# 60.net
KiCad netlist of a schematic drawn in EasyEDA Pro
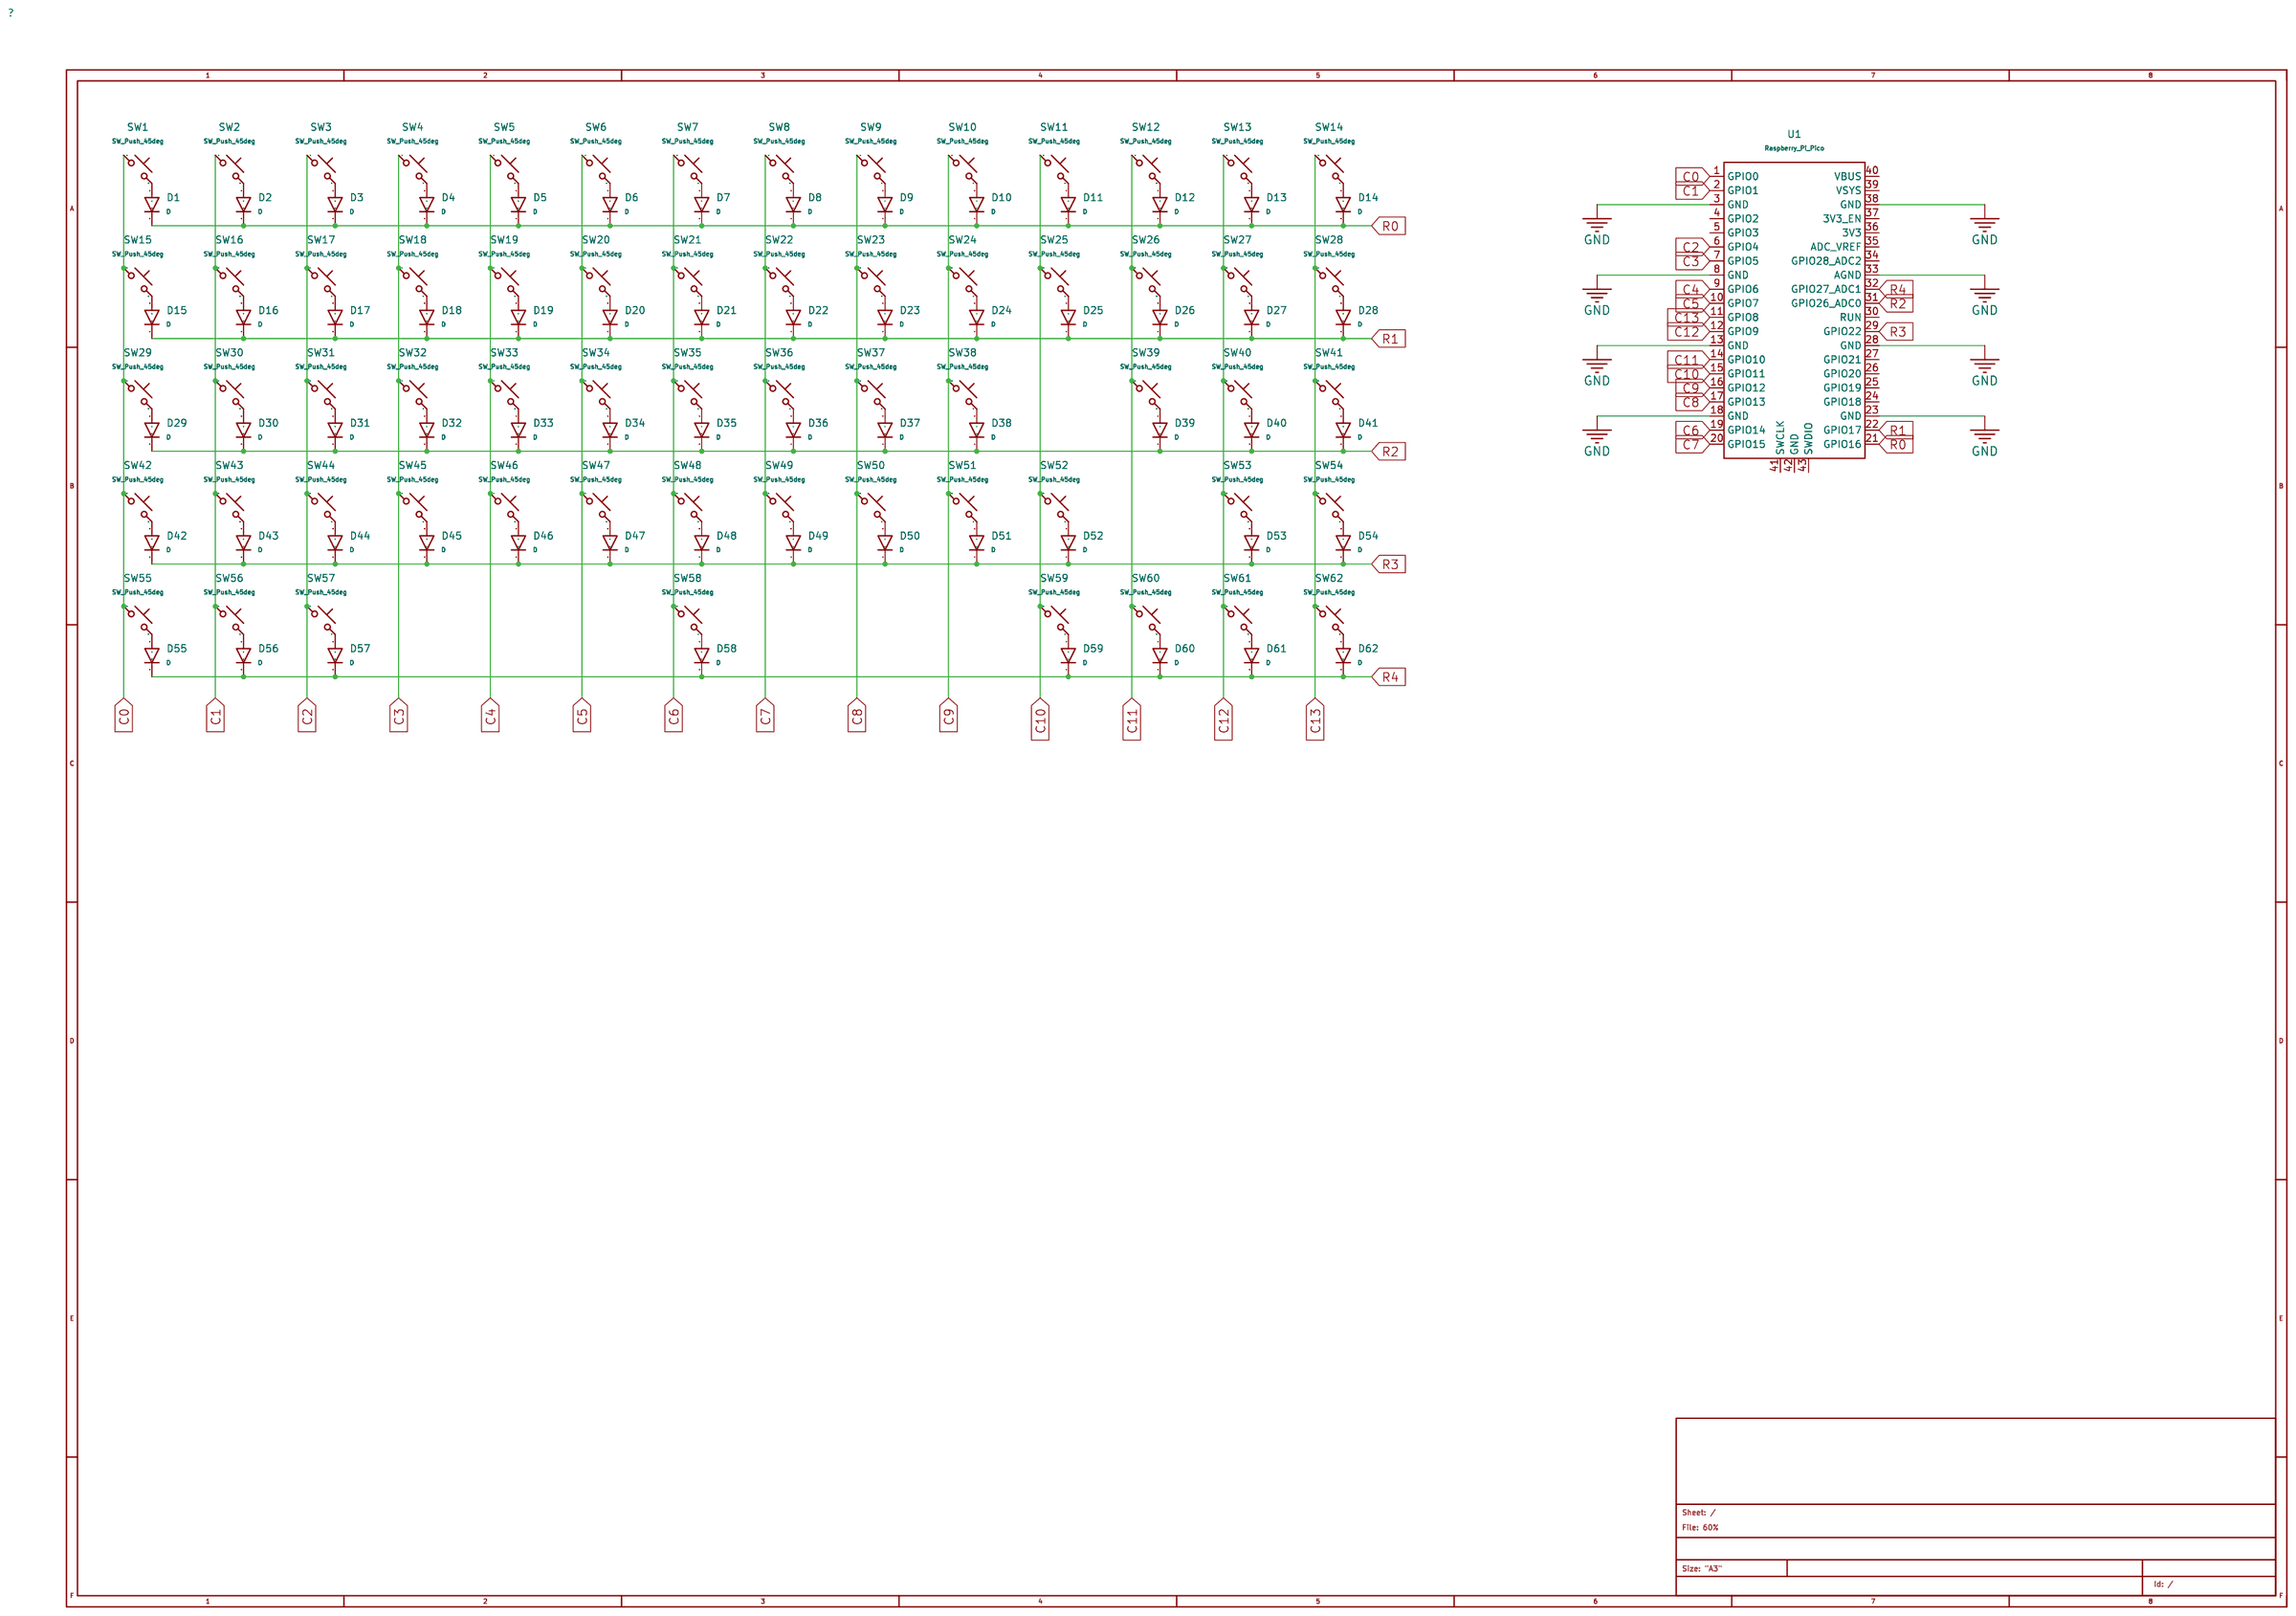
[diagram p0: schematic sheet]

(export (version "E")
  (design (tool "Eeschema 10.0.6"))
  (components
    (comp (ref "D1")
      (value "D")
      (footprint "easyedapro:Diode_DO-35")
      (description "Diode")
      (libsource (lib "easyedapro") (part "Device_D"))
    )
    (comp (ref "D2")
      (value "D")
      (footprint "easyedapro:Diode_DO-35")
      (description "Diode")
      (libsource (lib "easyedapro") (part "Device_D"))
    )
    (comp (ref "D3")
      (value "D")
      (footprint "easyedapro:Diode_DO-35")
      (description "Diode")
      (libsource (lib "easyedapro") (part "Device_D"))
    )
    (comp (ref "D4")
      (value "D")
      (footprint "easyedapro:Diode_DO-35")
      (description "Diode")
      (libsource (lib "easyedapro") (part "Device_D"))
    )
    (comp (ref "D5")
      (value "D")
      (footprint "easyedapro:Diode_DO-35")
      (description "Diode")
      (libsource (lib "easyedapro") (part "Device_D"))
    )
    (comp (ref "D6")
      (value "D")
      (footprint "easyedapro:Diode_DO-35")
      (description "Diode")
      (libsource (lib "easyedapro") (part "Device_D"))
    )
    (comp (ref "D7")
      (value "D")
      (footprint "easyedapro:Diode_DO-35")
      (description "Diode")
      (libsource (lib "easyedapro") (part "Device_D"))
    )
    (comp (ref "D8")
      (value "D")
      (footprint "easyedapro:Diode_DO-35")
      (description "Diode")
      (libsource (lib "easyedapro") (part "Device_D"))
    )
    (comp (ref "D9")
      (value "D")
      (footprint "easyedapro:Diode_DO-35")
      (description "Diode")
      (libsource (lib "easyedapro") (part "Device_D"))
    )
    (comp (ref "D10")
      (value "D")
      (footprint "easyedapro:Diode_DO-35")
      (description "Diode")
      (libsource (lib "easyedapro") (part "Device_D"))
    )
    (comp (ref "D11")
      (value "D")
      (footprint "easyedapro:Diode_DO-35")
      (description "Diode")
      (libsource (lib "easyedapro") (part "Device_D"))
    )
    (comp (ref "D12")
      (value "D")
      (footprint "easyedapro:Diode_DO-35")
      (description "Diode")
      (libsource (lib "easyedapro") (part "Device_D"))
    )
    (comp (ref "D13")
      (value "D")
      (footprint "easyedapro:Diode_DO-35")
      (description "Diode")
      (libsource (lib "easyedapro") (part "Device_D"))
    )
    (comp (ref "D14")
      (value "D")
      (footprint "easyedapro:Diode_DO-35")
      (description "Diode")
      (libsource (lib "easyedapro") (part "Device_D"))
    )
    (comp (ref "D15")
      (value "D")
      (footprint "easyedapro:Diode_DO-35")
      (description "Diode")
      (libsource (lib "easyedapro") (part "Device_D"))
    )
    (comp (ref "D16")
      (value "D")
      (footprint "easyedapro:Diode_DO-35")
      (description "Diode")
      (libsource (lib "easyedapro") (part "Device_D"))
    )
    (comp (ref "D17")
      (value "D")
      (footprint "easyedapro:Diode_DO-35")
      (description "Diode")
      (libsource (lib "easyedapro") (part "Device_D"))
    )
    (comp (ref "D18")
      (value "D")
      (footprint "easyedapro:Diode_DO-35")
      (description "Diode")
      (libsource (lib "easyedapro") (part "Device_D"))
    )
    (comp (ref "D19")
      (value "D")
      (footprint "easyedapro:Diode_DO-35")
      (description "Diode")
      (libsource (lib "easyedapro") (part "Device_D"))
    )
    (comp (ref "D20")
      (value "D")
      (footprint "easyedapro:Diode_DO-35")
      (description "Diode")
      (libsource (lib "easyedapro") (part "Device_D"))
    )
    (comp (ref "D21")
      (value "D")
      (footprint "easyedapro:Diode_DO-35")
      (description "Diode")
      (libsource (lib "easyedapro") (part "Device_D"))
    )
    (comp (ref "D22")
      (value "D")
      (footprint "easyedapro:Diode_DO-35")
      (description "Diode")
      (libsource (lib "easyedapro") (part "Device_D"))
    )
    (comp (ref "D23")
      (value "D")
      (footprint "easyedapro:Diode_DO-35")
      (description "Diode")
      (libsource (lib "easyedapro") (part "Device_D"))
    )
    (comp (ref "D24")
      (value "D")
      (footprint "easyedapro:Diode_DO-35")
      (description "Diode")
      (libsource (lib "easyedapro") (part "Device_D"))
    )
    (comp (ref "D25")
      (value "D")
      (footprint "easyedapro:Diode_DO-35")
      (description "Diode")
      (libsource (lib "easyedapro") (part "Device_D"))
    )
    (comp (ref "D26")
      (value "D")
      (footprint "easyedapro:Diode_DO-35")
      (description "Diode")
      (libsource (lib "easyedapro") (part "Device_D"))
    )
    (comp (ref "D27")
      (value "D")
      (footprint "easyedapro:Diode_DO-35")
      (description "Diode")
      (libsource (lib "easyedapro") (part "Device_D"))
    )
    (comp (ref "D28")
      (value "D")
      (footprint "easyedapro:Diode_DO-35")
      (description "Diode")
      (libsource (lib "easyedapro") (part "Device_D"))
    )
    (comp (ref "D29")
      (value "D")
      (footprint "easyedapro:Diode_DO-35")
      (description "Diode")
      (libsource (lib "easyedapro") (part "Device_D"))
    )
    (comp (ref "D30")
      (value "D")
      (footprint "easyedapro:Diode_DO-35")
      (description "Diode")
      (libsource (lib "easyedapro") (part "Device_D"))
    )
    (comp (ref "D31")
      (value "D")
      (footprint "easyedapro:Diode_DO-35")
      (description "Diode")
      (libsource (lib "easyedapro") (part "Device_D"))
    )
    (comp (ref "D32")
      (value "D")
      (footprint "easyedapro:Diode_DO-35")
      (description "Diode")
      (libsource (lib "easyedapro") (part "Device_D"))
    )
    (comp (ref "D33")
      (value "D")
      (footprint "easyedapro:Diode_DO-35")
      (description "Diode")
      (libsource (lib "easyedapro") (part "Device_D"))
    )
    (comp (ref "D34")
      (value "D")
      (footprint "easyedapro:Diode_DO-35")
      (description "Diode")
      (libsource (lib "easyedapro") (part "Device_D"))
    )
    (comp (ref "D35")
      (value "D")
      (footprint "easyedapro:Diode_DO-35")
      (description "Diode")
      (libsource (lib "easyedapro") (part "Device_D"))
    )
    (comp (ref "D36")
      (value "D")
      (footprint "easyedapro:Diode_DO-35")
      (description "Diode")
      (libsource (lib "easyedapro") (part "Device_D"))
    )
    (comp (ref "D37")
      (value "D")
      (footprint "easyedapro:Diode_DO-35")
      (description "Diode")
      (libsource (lib "easyedapro") (part "Device_D"))
    )
    (comp (ref "D38")
      (value "D")
      (footprint "easyedapro:Diode_DO-35")
      (description "Diode")
      (libsource (lib "easyedapro") (part "Device_D"))
    )
    (comp (ref "D39")
      (value "D")
      (footprint "easyedapro:Diode_DO-35")
      (description "Diode")
      (libsource (lib "easyedapro") (part "Device_D"))
    )
    (comp (ref "D40")
      (value "D")
      (footprint "easyedapro:Diode_DO-35")
      (description "Diode")
      (libsource (lib "easyedapro") (part "Device_D"))
    )
    (comp (ref "D41")
      (value "D")
      (footprint "easyedapro:Diode_DO-35")
      (description "Diode")
      (libsource (lib "easyedapro") (part "Device_D"))
    )
    (comp (ref "D42")
      (value "D")
      (footprint "easyedapro:Diode_DO-35")
      (description "Diode")
      (libsource (lib "easyedapro") (part "Device_D"))
    )
    (comp (ref "D43")
      (value "D")
      (footprint "easyedapro:Diode_DO-35")
      (description "Diode")
      (libsource (lib "easyedapro") (part "Device_D"))
    )
    (comp (ref "D44")
      (value "D")
      (footprint "easyedapro:Diode_DO-35")
      (description "Diode")
      (libsource (lib "easyedapro") (part "Device_D"))
    )
    (comp (ref "D45")
      (value "D")
      (footprint "easyedapro:Diode_DO-35")
      (description "Diode")
      (libsource (lib "easyedapro") (part "Device_D"))
    )
    (comp (ref "D46")
      (value "D")
      (footprint "easyedapro:Diode_DO-35")
      (description "Diode")
      (libsource (lib "easyedapro") (part "Device_D"))
    )
    (comp (ref "D47")
      (value "D")
      (footprint "easyedapro:Diode_DO-35")
      (description "Diode")
      (libsource (lib "easyedapro") (part "Device_D"))
    )
    (comp (ref "D48")
      (value "D")
      (footprint "easyedapro:Diode_DO-35")
      (description "Diode")
      (libsource (lib "easyedapro") (part "Device_D"))
    )
    (comp (ref "D49")
      (value "D")
      (footprint "easyedapro:Diode_DO-35")
      (description "Diode")
      (libsource (lib "easyedapro") (part "Device_D"))
    )
    (comp (ref "D50")
      (value "D")
      (footprint "easyedapro:Diode_DO-35")
      (description "Diode")
      (libsource (lib "easyedapro") (part "Device_D"))
    )
    (comp (ref "D51")
      (value "D")
      (footprint "easyedapro:Diode_DO-35")
      (description "Diode")
      (libsource (lib "easyedapro") (part "Device_D"))
    )
    (comp (ref "D52")
      (value "D")
      (footprint "easyedapro:Diode_DO-35")
      (description "Diode")
      (libsource (lib "easyedapro") (part "Device_D"))
    )
    (comp (ref "D53")
      (value "D")
      (footprint "easyedapro:Diode_DO-35")
      (description "Diode")
      (libsource (lib "easyedapro") (part "Device_D"))
    )
    (comp (ref "D54")
      (value "D")
      (footprint "easyedapro:Diode_DO-35")
      (description "Diode")
      (libsource (lib "easyedapro") (part "Device_D"))
    )
    (comp (ref "D55")
      (value "D")
      (footprint "easyedapro:Diode_DO-35")
      (description "Diode")
      (libsource (lib "easyedapro") (part "Device_D"))
    )
    (comp (ref "D56")
      (value "D")
      (footprint "easyedapro:Diode_DO-35")
      (description "Diode")
      (libsource (lib "easyedapro") (part "Device_D"))
    )
    (comp (ref "D57")
      (value "D")
      (footprint "easyedapro:Diode_DO-35")
      (description "Diode")
      (libsource (lib "easyedapro") (part "Device_D"))
    )
    (comp (ref "D58")
      (value "D")
      (footprint "easyedapro:Diode_DO-35")
      (description "Diode")
      (libsource (lib "easyedapro") (part "Device_D"))
    )
    (comp (ref "D59")
      (value "D")
      (footprint "easyedapro:Diode_DO-35")
      (description "Diode")
      (libsource (lib "easyedapro") (part "Device_D"))
    )
    (comp (ref "D60")
      (value "D")
      (footprint "easyedapro:Diode_DO-35")
      (description "Diode")
      (libsource (lib "easyedapro") (part "Device_D"))
    )
    (comp (ref "D61")
      (value "D")
      (footprint "easyedapro:Diode_DO-35")
      (description "Diode")
      (libsource (lib "easyedapro") (part "Device_D"))
    )
    (comp (ref "D62")
      (value "D")
      (footprint "easyedapro:Diode_DO-35")
      (description "Diode")
      (libsource (lib "easyedapro") (part "Device_D"))
    )
    (comp (ref "SW1")
      (value "SW_Push_45deg")
      (footprint "easyedapro:MX_PCB_1.00u")
      (description "Push button switch, normally open, two pins, 45° tilted")
      (libsource (lib "easyedapro") (part "Switch_SW_Push_45deg"))
    )
    (comp (ref "SW2")
      (value "SW_Push_45deg")
      (footprint "easyedapro:MX_PCB_1.00u")
      (description "Push button switch, normally open, two pins, 45° tilted")
      (libsource (lib "easyedapro") (part "Switch_SW_Push_45deg"))
    )
    (comp (ref "SW3")
      (value "SW_Push_45deg")
      (footprint "easyedapro:MX_PCB_1.00u")
      (description "Push button switch, normally open, two pins, 45° tilted")
      (libsource (lib "easyedapro") (part "Switch_SW_Push_45deg"))
    )
    (comp (ref "SW4")
      (value "SW_Push_45deg")
      (footprint "easyedapro:MX_PCB_1.00u")
      (description "Push button switch, normally open, two pins, 45° tilted")
      (libsource (lib "easyedapro") (part "Switch_SW_Push_45deg"))
    )
    (comp (ref "SW5")
      (value "SW_Push_45deg")
      (footprint "easyedapro:MX_PCB_1.00u")
      (description "Push button switch, normally open, two pins, 45° tilted")
      (libsource (lib "easyedapro") (part "Switch_SW_Push_45deg"))
    )
    (comp (ref "SW6")
      (value "SW_Push_45deg")
      (footprint "easyedapro:MX_PCB_1.00u")
      (description "Push button switch, normally open, two pins, 45° tilted")
      (libsource (lib "easyedapro") (part "Switch_SW_Push_45deg"))
    )
    (comp (ref "SW7")
      (value "SW_Push_45deg")
      (footprint "easyedapro:MX_PCB_1.00u")
      (description "Push button switch, normally open, two pins, 45° tilted")
      (libsource (lib "easyedapro") (part "Switch_SW_Push_45deg"))
    )
    (comp (ref "SW8")
      (value "SW_Push_45deg")
      (footprint "easyedapro:MX_PCB_1.00u")
      (description "Push button switch, normally open, two pins, 45° tilted")
      (libsource (lib "easyedapro") (part "Switch_SW_Push_45deg"))
    )
    (comp (ref "SW9")
      (value "SW_Push_45deg")
      (footprint "easyedapro:MX_PCB_1.00u")
      (description "Push button switch, normally open, two pins, 45° tilted")
      (libsource (lib "easyedapro") (part "Switch_SW_Push_45deg"))
    )
    (comp (ref "SW10")
      (value "SW_Push_45deg")
      (footprint "easyedapro:MX_PCB_1.00u")
      (description "Push button switch, normally open, two pins, 45° tilted")
      (libsource (lib "easyedapro") (part "Switch_SW_Push_45deg"))
    )
    (comp (ref "SW11")
      (value "SW_Push_45deg")
      (footprint "easyedapro:MX_PCB_1.00u")
      (description "Push button switch, normally open, two pins, 45° tilted")
      (libsource (lib "easyedapro") (part "Switch_SW_Push_45deg"))
    )
    (comp (ref "SW12")
      (value "SW_Push_45deg")
      (footprint "easyedapro:MX_PCB_1.00u")
      (description "Push button switch, normally open, two pins, 45° tilted")
      (libsource (lib "easyedapro") (part "Switch_SW_Push_45deg"))
    )
    (comp (ref "SW13")
      (value "SW_Push_45deg")
      (footprint "easyedapro:MX_PCB_1.00u")
      (description "Push button switch, normally open, two pins, 45° tilted")
      (libsource (lib "easyedapro") (part "Switch_SW_Push_45deg"))
    )
    (comp (ref "SW14")
      (value "SW_Push_45deg")
      (footprint "easyedapro:MX_PCB_1.00u")
      (description "Push button switch, normally open, two pins, 45° tilted")
      (libsource (lib "easyedapro") (part "Switch_SW_Push_45deg"))
    )
    (comp (ref "SW15")
      (value "SW_Push_45deg")
      (footprint "easyedapro:MX_PCB_1.00u")
      (description "Push button switch, normally open, two pins, 45° tilted")
      (libsource (lib "easyedapro") (part "Switch_SW_Push_45deg"))
    )
    (comp (ref "SW16")
      (value "SW_Push_45deg")
      (footprint "easyedapro:MX_PCB_1.00u")
      (description "Push button switch, normally open, two pins, 45° tilted")
      (libsource (lib "easyedapro") (part "Switch_SW_Push_45deg"))
    )
    (comp (ref "SW17")
      (value "SW_Push_45deg")
      (footprint "easyedapro:MX_PCB_1.00u")
      (description "Push button switch, normally open, two pins, 45° tilted")
      (libsource (lib "easyedapro") (part "Switch_SW_Push_45deg"))
    )
    (comp (ref "SW18")
      (value "SW_Push_45deg")
      (footprint "easyedapro:MX_PCB_1.00u")
      (description "Push button switch, normally open, two pins, 45° tilted")
      (libsource (lib "easyedapro") (part "Switch_SW_Push_45deg"))
    )
    (comp (ref "SW19")
      (value "SW_Push_45deg")
      (footprint "easyedapro:MX_PCB_1.00u")
      (description "Push button switch, normally open, two pins, 45° tilted")
      (libsource (lib "easyedapro") (part "Switch_SW_Push_45deg"))
    )
    (comp (ref "SW20")
      (value "SW_Push_45deg")
      (footprint "easyedapro:MX_PCB_1.00u")
      (description "Push button switch, normally open, two pins, 45° tilted")
      (libsource (lib "easyedapro") (part "Switch_SW_Push_45deg"))
    )
    (comp (ref "SW21")
      (value "SW_Push_45deg")
      (footprint "easyedapro:MX_PCB_1.00u")
      (description "Push button switch, normally open, two pins, 45° tilted")
      (libsource (lib "easyedapro") (part "Switch_SW_Push_45deg"))
    )
    (comp (ref "SW22")
      (value "SW_Push_45deg")
      (footprint "easyedapro:MX_PCB_1.00u")
      (description "Push button switch, normally open, two pins, 45° tilted")
      (libsource (lib "easyedapro") (part "Switch_SW_Push_45deg"))
    )
    (comp (ref "SW23")
      (value "SW_Push_45deg")
      (footprint "easyedapro:MX_PCB_1.00u")
      (description "Push button switch, normally open, two pins, 45° tilted")
      (libsource (lib "easyedapro") (part "Switch_SW_Push_45deg"))
    )
    (comp (ref "SW24")
      (value "SW_Push_45deg")
      (footprint "easyedapro:MX_PCB_1.00u")
      (description "Push button switch, normally open, two pins, 45° tilted")
      (libsource (lib "easyedapro") (part "Switch_SW_Push_45deg"))
    )
    (comp (ref "SW25")
      (value "SW_Push_45deg")
      (footprint "easyedapro:MX_PCB_1.00u")
      (description "Push button switch, normally open, two pins, 45° tilted")
      (libsource (lib "easyedapro") (part "Switch_SW_Push_45deg"))
    )
    (comp (ref "SW26")
      (value "SW_Push_45deg")
      (footprint "easyedapro:MX_PCB_1.00u")
      (description "Push button switch, normally open, two pins, 45° tilted")
      (libsource (lib "easyedapro") (part "Switch_SW_Push_45deg"))
    )
    (comp (ref "SW27")
      (value "SW_Push_45deg")
      (footprint "easyedapro:MX_PCB_1.00u")
      (description "Push button switch, normally open, two pins, 45° tilted")
      (libsource (lib "easyedapro") (part "Switch_SW_Push_45deg"))
    )
    (comp (ref "SW28")
      (value "SW_Push_45deg")
      (footprint "easyedapro:MX_PCB_1.00u")
      (description "Push button switch, normally open, two pins, 45° tilted")
      (libsource (lib "easyedapro") (part "Switch_SW_Push_45deg"))
    )
    (comp (ref "SW29")
      (value "SW_Push_45deg")
      (footprint "easyedapro:MX_PCB_1.00u")
      (description "Push button switch, normally open, two pins, 45° tilted")
      (libsource (lib "easyedapro") (part "Switch_SW_Push_45deg"))
    )
    (comp (ref "SW30")
      (value "SW_Push_45deg")
      (footprint "easyedapro:MX_PCB_1.00u")
      (description "Push button switch, normally open, two pins, 45° tilted")
      (libsource (lib "easyedapro") (part "Switch_SW_Push_45deg"))
    )
    (comp (ref "SW31")
      (value "SW_Push_45deg")
      (footprint "easyedapro:MX_PCB_1.00u")
      (description "Push button switch, normally open, two pins, 45° tilted")
      (libsource (lib "easyedapro") (part "Switch_SW_Push_45deg"))
    )
    (comp (ref "SW32")
      (value "SW_Push_45deg")
      (footprint "easyedapro:MX_PCB_1.00u")
      (description "Push button switch, normally open, two pins, 45° tilted")
      (libsource (lib "easyedapro") (part "Switch_SW_Push_45deg"))
    )
    (comp (ref "SW33")
      (value "SW_Push_45deg")
      (footprint "easyedapro:MX_PCB_1.00u")
      (description "Push button switch, normally open, two pins, 45° tilted")
      (libsource (lib "easyedapro") (part "Switch_SW_Push_45deg"))
    )
    (comp (ref "SW34")
      (value "SW_Push_45deg")
      (footprint "easyedapro:MX_PCB_1.00u")
      (description "Push button switch, normally open, two pins, 45° tilted")
      (libsource (lib "easyedapro") (part "Switch_SW_Push_45deg"))
    )
    (comp (ref "SW35")
      (value "SW_Push_45deg")
      (footprint "easyedapro:MX_PCB_1.00u")
      (description "Push button switch, normally open, two pins, 45° tilted")
      (libsource (lib "easyedapro") (part "Switch_SW_Push_45deg"))
    )
    (comp (ref "SW36")
      (value "SW_Push_45deg")
      (footprint "easyedapro:MX_PCB_1.00u")
      (description "Push button switch, normally open, two pins, 45° tilted")
      (libsource (lib "easyedapro") (part "Switch_SW_Push_45deg"))
    )
    (comp (ref "SW37")
      (value "SW_Push_45deg")
      (footprint "easyedapro:MX_PCB_1.00u")
      (description "Push button switch, normally open, two pins, 45° tilted")
      (libsource (lib "easyedapro") (part "Switch_SW_Push_45deg"))
    )
    (comp (ref "SW38")
      (value "SW_Push_45deg")
      (footprint "easyedapro:MX_PCB_1.00u")
      (description "Push button switch, normally open, two pins, 45° tilted")
      (libsource (lib "easyedapro") (part "Switch_SW_Push_45deg"))
    )
    (comp (ref "SW39")
      (value "SW_Push_45deg")
      (footprint "easyedapro:MX_PCB_1.00u")
      (description "Push button switch, normally open, two pins, 45° tilted")
      (libsource (lib "easyedapro") (part "Switch_SW_Push_45deg"))
    )
    (comp (ref "SW40")
      (value "SW_Push_45deg")
      (footprint "easyedapro:MX_PCB_1.00u")
      (description "Push button switch, normally open, two pins, 45° tilted")
      (libsource (lib "easyedapro") (part "Switch_SW_Push_45deg"))
    )
    (comp (ref "SW41")
      (value "SW_Push_45deg")
      (footprint "easyedapro:MX_PCB_1.00u")
      (description "Push button switch, normally open, two pins, 45° tilted")
      (libsource (lib "easyedapro") (part "Switch_SW_Push_45deg"))
    )
    (comp (ref "SW42")
      (value "SW_Push_45deg")
      (footprint "easyedapro:MX_PCB_1.00u")
      (description "Push button switch, normally open, two pins, 45° tilted")
      (libsource (lib "easyedapro") (part "Switch_SW_Push_45deg"))
    )
    (comp (ref "SW43")
      (value "SW_Push_45deg")
      (footprint "easyedapro:MX_PCB_1.00u")
      (description "Push button switch, normally open, two pins, 45° tilted")
      (libsource (lib "easyedapro") (part "Switch_SW_Push_45deg"))
    )
    (comp (ref "SW44")
      (value "SW_Push_45deg")
      (footprint "easyedapro:MX_PCB_1.00u")
      (description "Push button switch, normally open, two pins, 45° tilted")
      (libsource (lib "easyedapro") (part "Switch_SW_Push_45deg"))
    )
    (comp (ref "SW45")
      (value "SW_Push_45deg")
      (footprint "easyedapro:MX_PCB_1.00u")
      (description "Push button switch, normally open, two pins, 45° tilted")
      (libsource (lib "easyedapro") (part "Switch_SW_Push_45deg"))
    )
    (comp (ref "SW46")
      (value "SW_Push_45deg")
      (footprint "easyedapro:MX_PCB_1.00u")
      (description "Push button switch, normally open, two pins, 45° tilted")
      (libsource (lib "easyedapro") (part "Switch_SW_Push_45deg"))
    )
    (comp (ref "SW47")
      (value "SW_Push_45deg")
      (footprint "easyedapro:MX_PCB_1.00u")
      (description "Push button switch, normally open, two pins, 45° tilted")
      (libsource (lib "easyedapro") (part "Switch_SW_Push_45deg"))
    )
    (comp (ref "SW48")
      (value "SW_Push_45deg")
      (footprint "easyedapro:MX_PCB_1.00u")
      (description "Push button switch, normally open, two pins, 45° tilted")
      (libsource (lib "easyedapro") (part "Switch_SW_Push_45deg"))
    )
    (comp (ref "SW49")
      (value "SW_Push_45deg")
      (footprint "easyedapro:MX_PCB_1.00u")
      (description "Push button switch, normally open, two pins, 45° tilted")
      (libsource (lib "easyedapro") (part "Switch_SW_Push_45deg"))
    )
    (comp (ref "SW50")
      (value "SW_Push_45deg")
      (footprint "easyedapro:MX_PCB_1.00u")
      (description "Push button switch, normally open, two pins, 45° tilted")
      (libsource (lib "easyedapro") (part "Switch_SW_Push_45deg"))
    )
    (comp (ref "SW51")
      (value "SW_Push_45deg")
      (footprint "easyedapro:MX_PCB_1.00u")
      (description "Push button switch, normally open, two pins, 45° tilted")
      (libsource (lib "easyedapro") (part "Switch_SW_Push_45deg"))
    )
    (comp (ref "SW52")
      (value "SW_Push_45deg")
      (footprint "easyedapro:MX_PCB_1.00u")
      (description "Push button switch, normally open, two pins, 45° tilted")
      (libsource (lib "easyedapro") (part "Switch_SW_Push_45deg"))
    )
    (comp (ref "SW53")
      (value "SW_Push_45deg")
      (footprint "easyedapro:MX_PCB_1.00u")
      (description "Push button switch, normally open, two pins, 45° tilted")
      (libsource (lib "easyedapro") (part "Switch_SW_Push_45deg"))
    )
    (comp (ref "SW54")
      (value "SW_Push_45deg")
      (footprint "easyedapro:MX_PCB_1.00u")
      (description "Push button switch, normally open, two pins, 45° tilted")
      (libsource (lib "easyedapro") (part "Switch_SW_Push_45deg"))
    )
    (comp (ref "SW55")
      (value "SW_Push_45deg")
      (footprint "easyedapro:MX_PCB_1.00u")
      (description "Push button switch, normally open, two pins, 45° tilted")
      (libsource (lib "easyedapro") (part "Switch_SW_Push_45deg"))
    )
    (comp (ref "SW56")
      (value "SW_Push_45deg")
      (footprint "easyedapro:MX_PCB_1.00u")
      (description "Push button switch, normally open, two pins, 45° tilted")
      (libsource (lib "easyedapro") (part "Switch_SW_Push_45deg"))
    )
    (comp (ref "SW57")
      (value "SW_Push_45deg")
      (footprint "easyedapro:MX_PCB_1.00u")
      (description "Push button switch, normally open, two pins, 45° tilted")
      (libsource (lib "easyedapro") (part "Switch_SW_Push_45deg"))
    )
    (comp (ref "SW58")
      (value "SW_Push_45deg")
      (footprint "easyedapro:MX_PCB_1.00u")
      (description "Push button switch, normally open, two pins, 45° tilted")
      (libsource (lib "easyedapro") (part "Switch_SW_Push_45deg"))
    )
    (comp (ref "SW59")
      (value "SW_Push_45deg")
      (footprint "easyedapro:MX_PCB_1.00u")
      (description "Push button switch, normally open, two pins, 45° tilted")
      (libsource (lib "easyedapro") (part "Switch_SW_Push_45deg"))
    )
    (comp (ref "SW60")
      (value "SW_Push_45deg")
      (footprint "easyedapro:MX_PCB_1.00u")
      (description "Push button switch, normally open, two pins, 45° tilted")
      (libsource (lib "easyedapro") (part "Switch_SW_Push_45deg"))
    )
    (comp (ref "SW61")
      (value "SW_Push_45deg")
      (footprint "easyedapro:MX_PCB_1.00u")
      (description "Push button switch, normally open, two pins, 45° tilted")
      (libsource (lib "easyedapro") (part "Switch_SW_Push_45deg"))
    )
    (comp (ref "SW62")
      (value "SW_Push_45deg")
      (footprint "easyedapro:MX_PCB_1.00u")
      (description "Push button switch, normally open, two pins, 45° tilted")
      (libsource (lib "easyedapro") (part "Switch_SW_Push_45deg"))
    )
    (comp (ref "U1")
      (value "Raspberry_Pi_Pico")
      (footprint "easyedapro:Raspberry_Pi_Pico")
      (libsource (lib "easyedapro") (part "ScottoKeebs_MCU_Raspberry_Pi_Pico"))
    )
  )
  (nets
    (net (code "1") (name "C0") (class "Default")
      (node (ref "SW1") (pin "1") (pinfunction "1_1") (pintype "unspecified"))
      (node (ref "SW15") (pin "1") (pinfunction "1_1") (pintype "unspecified"))
      (node (ref "SW29") (pin "1") (pinfunction "1_1") (pintype "unspecified"))
      (node (ref "SW42") (pin "1") (pinfunction "1_1") (pintype "unspecified"))
      (node (ref "SW55") (pin "1") (pinfunction "1_1") (pintype "unspecified"))
      (node (ref "U1") (pin "1") (pinfunction "GPIO0_1") (pintype "bidirectional"))
    )
    (net (code "2") (name "C1") (class "Default")
      (node (ref "SW16") (pin "1") (pinfunction "1_1") (pintype "unspecified"))
      (node (ref "SW2") (pin "1") (pinfunction "1_1") (pintype "unspecified"))
      (node (ref "SW30") (pin "1") (pinfunction "1_1") (pintype "unspecified"))
      (node (ref "SW43") (pin "1") (pinfunction "1_1") (pintype "unspecified"))
      (node (ref "SW56") (pin "1") (pinfunction "1_1") (pintype "unspecified"))
      (node (ref "U1") (pin "2") (pinfunction "GPIO1_2") (pintype "bidirectional"))
    )
    (net (code "3") (name "C2") (class "Default")
      (node (ref "SW17") (pin "1") (pinfunction "1_1") (pintype "unspecified"))
      (node (ref "SW3") (pin "1") (pinfunction "1_1") (pintype "unspecified"))
      (node (ref "SW31") (pin "1") (pinfunction "1_1") (pintype "unspecified"))
      (node (ref "SW44") (pin "1") (pinfunction "1_1") (pintype "unspecified"))
      (node (ref "SW57") (pin "1") (pinfunction "1_1") (pintype "unspecified"))
      (node (ref "U1") (pin "6") (pinfunction "GPIO4_6") (pintype "bidirectional"))
    )
    (net (code "4") (name "C3") (class "Default")
      (node (ref "SW18") (pin "1") (pinfunction "1_1") (pintype "unspecified"))
      (node (ref "SW32") (pin "1") (pinfunction "1_1") (pintype "unspecified"))
      (node (ref "SW4") (pin "1") (pinfunction "1_1") (pintype "unspecified"))
      (node (ref "SW45") (pin "1") (pinfunction "1_1") (pintype "unspecified"))
      (node (ref "U1") (pin "7") (pinfunction "GPIO5_7") (pintype "bidirectional"))
    )
    (net (code "5") (name "C4") (class "Default")
      (node (ref "SW19") (pin "1") (pinfunction "1_1") (pintype "unspecified"))
      (node (ref "SW33") (pin "1") (pinfunction "1_1") (pintype "unspecified"))
      (node (ref "SW46") (pin "1") (pinfunction "1_1") (pintype "unspecified"))
      (node (ref "SW5") (pin "1") (pinfunction "1_1") (pintype "unspecified"))
      (node (ref "U1") (pin "9") (pinfunction "GPIO6_9") (pintype "bidirectional"))
    )
    (net (code "6") (name "C5") (class "Default")
      (node (ref "SW20") (pin "1") (pinfunction "1_1") (pintype "unspecified"))
      (node (ref "SW34") (pin "1") (pinfunction "1_1") (pintype "unspecified"))
      (node (ref "SW47") (pin "1") (pinfunction "1_1") (pintype "unspecified"))
      (node (ref "SW6") (pin "1") (pinfunction "1_1") (pintype "unspecified"))
      (node (ref "U1") (pin "10") (pinfunction "GPIO7_10") (pintype "bidirectional"))
    )
    (net (code "7") (name "C6") (class "Default")
      (node (ref "SW21") (pin "1") (pinfunction "1_1") (pintype "unspecified"))
      (node (ref "SW35") (pin "1") (pinfunction "1_1") (pintype "unspecified"))
      (node (ref "SW48") (pin "1") (pinfunction "1_1") (pintype "unspecified"))
      (node (ref "SW58") (pin "1") (pinfunction "1_1") (pintype "unspecified"))
      (node (ref "SW7") (pin "1") (pinfunction "1_1") (pintype "unspecified"))
      (node (ref "U1") (pin "19") (pinfunction "GPIO14_19") (pintype "bidirectional"))
    )
    (net (code "8") (name "C7") (class "Default")
      (node (ref "SW22") (pin "1") (pinfunction "1_1") (pintype "unspecified"))
      (node (ref "SW36") (pin "1") (pinfunction "1_1") (pintype "unspecified"))
      (node (ref "SW49") (pin "1") (pinfunction "1_1") (pintype "unspecified"))
      (node (ref "SW8") (pin "1") (pinfunction "1_1") (pintype "unspecified"))
      (node (ref "U1") (pin "20") (pinfunction "GPIO15_20") (pintype "bidirectional"))
    )
    (net (code "9") (name "C8") (class "Default")
      (node (ref "SW23") (pin "1") (pinfunction "1_1") (pintype "unspecified"))
      (node (ref "SW37") (pin "1") (pinfunction "1_1") (pintype "unspecified"))
      (node (ref "SW50") (pin "1") (pinfunction "1_1") (pintype "unspecified"))
      (node (ref "SW9") (pin "1") (pinfunction "1_1") (pintype "unspecified"))
      (node (ref "U1") (pin "17") (pinfunction "GPIO13_17") (pintype "bidirectional"))
    )
    (net (code "10") (name "C9") (class "Default")
      (node (ref "SW10") (pin "1") (pinfunction "1_1") (pintype "unspecified"))
      (node (ref "SW24") (pin "1") (pinfunction "1_1") (pintype "unspecified"))
      (node (ref "SW38") (pin "1") (pinfunction "1_1") (pintype "unspecified"))
      (node (ref "SW51") (pin "1") (pinfunction "1_1") (pintype "unspecified"))
      (node (ref "U1") (pin "16") (pinfunction "GPIO12_16") (pintype "bidirectional"))
    )
    (net (code "11") (name "C10") (class "Default")
      (node (ref "SW11") (pin "1") (pinfunction "1_1") (pintype "unspecified"))
      (node (ref "SW25") (pin "1") (pinfunction "1_1") (pintype "unspecified"))
      (node (ref "SW52") (pin "1") (pinfunction "1_1") (pintype "unspecified"))
      (node (ref "SW59") (pin "1") (pinfunction "1_1") (pintype "unspecified"))
      (node (ref "U1") (pin "15") (pinfunction "GPIO11_15") (pintype "bidirectional"))
    )
    (net (code "12") (name "C11") (class "Default")
      (node (ref "SW12") (pin "1") (pinfunction "1_1") (pintype "unspecified"))
      (node (ref "SW26") (pin "1") (pinfunction "1_1") (pintype "unspecified"))
      (node (ref "SW39") (pin "1") (pinfunction "1_1") (pintype "unspecified"))
      (node (ref "SW60") (pin "1") (pinfunction "1_1") (pintype "unspecified"))
      (node (ref "U1") (pin "14") (pinfunction "GPIO10_14") (pintype "bidirectional"))
    )
    (net (code "13") (name "C12") (class "Default")
      (node (ref "SW13") (pin "1") (pinfunction "1_1") (pintype "unspecified"))
      (node (ref "SW27") (pin "1") (pinfunction "1_1") (pintype "unspecified"))
      (node (ref "SW40") (pin "1") (pinfunction "1_1") (pintype "unspecified"))
      (node (ref "SW53") (pin "1") (pinfunction "1_1") (pintype "unspecified"))
      (node (ref "SW61") (pin "1") (pinfunction "1_1") (pintype "unspecified"))
      (node (ref "U1") (pin "12") (pinfunction "GPIO9_12") (pintype "bidirectional"))
    )
    (net (code "14") (name "C13") (class "Default")
      (node (ref "SW14") (pin "1") (pinfunction "1_1") (pintype "unspecified"))
      (node (ref "SW28") (pin "1") (pinfunction "1_1") (pintype "unspecified"))
      (node (ref "SW41") (pin "1") (pinfunction "1_1") (pintype "unspecified"))
      (node (ref "SW54") (pin "1") (pinfunction "1_1") (pintype "unspecified"))
      (node (ref "SW62") (pin "1") (pinfunction "1_1") (pintype "unspecified"))
      (node (ref "U1") (pin "11") (pinfunction "GPIO8_11") (pintype "bidirectional"))
    )
    (net (code "15") (name "GND") (class "Default")
      (node (ref "U1") (pin "13") (pinfunction "GND_13") (pintype "unspecified"))
      (node (ref "U1") (pin "18") (pinfunction "GND_18") (pintype "unspecified"))
      (node (ref "U1") (pin "23") (pinfunction "GND_23") (pintype "unspecified"))
      (node (ref "U1") (pin "28") (pinfunction "GND_28") (pintype "unspecified"))
      (node (ref "U1") (pin "3") (pinfunction "GND_3") (pintype "unspecified"))
      (node (ref "U1") (pin "33") (pinfunction "AGND_33") (pintype "unspecified"))
      (node (ref "U1") (pin "38") (pinfunction "GND_38") (pintype "bidirectional"))
      (node (ref "U1") (pin "8") (pinfunction "GND_8") (pintype "unspecified"))
    )
    (net (code "16") (name "Net-(D1-A)") (class "Default")
      (node (ref "D1") (pin "2") (pinfunction "A_2") (pintype "unspecified"))
      (node (ref "SW1") (pin "2") (pinfunction "2_2") (pintype "unspecified"))
    )
    (net (code "17") (name "Net-(D2-A)") (class "Default")
      (node (ref "D2") (pin "2") (pinfunction "A_2") (pintype "unspecified"))
      (node (ref "SW2") (pin "2") (pinfunction "2_2") (pintype "unspecified"))
    )
    (net (code "18") (name "Net-(D3-A)") (class "Default")
      (node (ref "D3") (pin "2") (pinfunction "A_2") (pintype "unspecified"))
      (node (ref "SW3") (pin "2") (pinfunction "2_2") (pintype "unspecified"))
    )
    (net (code "19") (name "Net-(D4-A)") (class "Default")
      (node (ref "D4") (pin "2") (pinfunction "A_2") (pintype "unspecified"))
      (node (ref "SW4") (pin "2") (pinfunction "2_2") (pintype "unspecified"))
    )
    (net (code "20") (name "Net-(D5-A)") (class "Default")
      (node (ref "D5") (pin "2") (pinfunction "A_2") (pintype "unspecified"))
      (node (ref "SW5") (pin "2") (pinfunction "2_2") (pintype "unspecified"))
    )
    (net (code "21") (name "Net-(D6-A)") (class "Default")
      (node (ref "D6") (pin "2") (pinfunction "A_2") (pintype "unspecified"))
      (node (ref "SW6") (pin "2") (pinfunction "2_2") (pintype "unspecified"))
    )
    (net (code "22") (name "Net-(D7-A)") (class "Default")
      (node (ref "D7") (pin "2") (pinfunction "A_2") (pintype "unspecified"))
      (node (ref "SW7") (pin "2") (pinfunction "2_2") (pintype "unspecified"))
    )
    (net (code "23") (name "Net-(D8-A)") (class "Default")
      (node (ref "D8") (pin "2") (pinfunction "A_2") (pintype "unspecified"))
      (node (ref "SW8") (pin "2") (pinfunction "2_2") (pintype "unspecified"))
    )
    (net (code "24") (name "Net-(D9-A)") (class "Default")
      (node (ref "D9") (pin "2") (pinfunction "A_2") (pintype "unspecified"))
      (node (ref "SW9") (pin "2") (pinfunction "2_2") (pintype "unspecified"))
    )
    (net (code "25") (name "Net-(D10-A)") (class "Default")
      (node (ref "D10") (pin "2") (pinfunction "A_2") (pintype "unspecified"))
      (node (ref "SW10") (pin "2") (pinfunction "2_2") (pintype "unspecified"))
    )
    (net (code "26") (name "Net-(D11-A)") (class "Default")
      (node (ref "D11") (pin "2") (pinfunction "A_2") (pintype "unspecified"))
      (node (ref "SW11") (pin "2") (pinfunction "2_2") (pintype "unspecified"))
    )
    (net (code "27") (name "Net-(D12-A)") (class "Default")
      (node (ref "D12") (pin "2") (pinfunction "A_2") (pintype "unspecified"))
      (node (ref "SW12") (pin "2") (pinfunction "2_2") (pintype "unspecified"))
    )
    (net (code "28") (name "Net-(D13-A)") (class "Default")
      (node (ref "D13") (pin "2") (pinfunction "A_2") (pintype "unspecified"))
      (node (ref "SW13") (pin "2") (pinfunction "2_2") (pintype "unspecified"))
    )
    (net (code "29") (name "Net-(D14-A)") (class "Default")
      (node (ref "D14") (pin "2") (pinfunction "A_2") (pintype "unspecified"))
      (node (ref "SW14") (pin "2") (pinfunction "2_2") (pintype "unspecified"))
    )
    (net (code "30") (name "Net-(D15-A)") (class "Default")
      (node (ref "D15") (pin "2") (pinfunction "A_2") (pintype "unspecified"))
      (node (ref "SW15") (pin "2") (pinfunction "2_2") (pintype "unspecified"))
    )
    (net (code "31") (name "Net-(D16-A)") (class "Default")
      (node (ref "D16") (pin "2") (pinfunction "A_2") (pintype "unspecified"))
      (node (ref "SW16") (pin "2") (pinfunction "2_2") (pintype "unspecified"))
    )
    (net (code "32") (name "Net-(D17-A)") (class "Default")
      (node (ref "D17") (pin "2") (pinfunction "A_2") (pintype "unspecified"))
      (node (ref "SW17") (pin "2") (pinfunction "2_2") (pintype "unspecified"))
    )
    (net (code "33") (name "Net-(D18-A)") (class "Default")
      (node (ref "D18") (pin "2") (pinfunction "A_2") (pintype "unspecified"))
      (node (ref "SW18") (pin "2") (pinfunction "2_2") (pintype "unspecified"))
    )
    (net (code "34") (name "Net-(D19-A)") (class "Default")
      (node (ref "D19") (pin "2") (pinfunction "A_2") (pintype "unspecified"))
      (node (ref "SW19") (pin "2") (pinfunction "2_2") (pintype "unspecified"))
    )
    (net (code "35") (name "Net-(D20-A)") (class "Default")
      (node (ref "D20") (pin "2") (pinfunction "A_2") (pintype "unspecified"))
      (node (ref "SW20") (pin "2") (pinfunction "2_2") (pintype "unspecified"))
    )
    (net (code "36") (name "Net-(D21-A)") (class "Default")
      (node (ref "D21") (pin "2") (pinfunction "A_2") (pintype "unspecified"))
      (node (ref "SW21") (pin "2") (pinfunction "2_2") (pintype "unspecified"))
    )
    (net (code "37") (name "Net-(D22-A)") (class "Default")
      (node (ref "D22") (pin "2") (pinfunction "A_2") (pintype "unspecified"))
      (node (ref "SW22") (pin "2") (pinfunction "2_2") (pintype "unspecified"))
    )
    (net (code "38") (name "Net-(D23-A)") (class "Default")
      (node (ref "D23") (pin "2") (pinfunction "A_2") (pintype "unspecified"))
      (node (ref "SW23") (pin "2") (pinfunction "2_2") (pintype "unspecified"))
    )
    (net (code "39") (name "Net-(D24-A)") (class "Default")
      (node (ref "D24") (pin "2") (pinfunction "A_2") (pintype "unspecified"))
      (node (ref "SW24") (pin "2") (pinfunction "2_2") (pintype "unspecified"))
    )
    (net (code "40") (name "Net-(D25-A)") (class "Default")
      (node (ref "D25") (pin "2") (pinfunction "A_2") (pintype "unspecified"))
      (node (ref "SW25") (pin "2") (pinfunction "2_2") (pintype "unspecified"))
    )
    (net (code "41") (name "Net-(D26-A)") (class "Default")
      (node (ref "D26") (pin "2") (pinfunction "A_2") (pintype "unspecified"))
      (node (ref "SW26") (pin "2") (pinfunction "2_2") (pintype "unspecified"))
    )
    (net (code "42") (name "Net-(D27-A)") (class "Default")
      (node (ref "D27") (pin "2") (pinfunction "A_2") (pintype "unspecified"))
      (node (ref "SW27") (pin "2") (pinfunction "2_2") (pintype "unspecified"))
    )
    (net (code "43") (name "Net-(D28-A)") (class "Default")
      (node (ref "D28") (pin "2") (pinfunction "A_2") (pintype "unspecified"))
      (node (ref "SW28") (pin "2") (pinfunction "2_2") (pintype "unspecified"))
    )
    (net (code "44") (name "Net-(D29-A)") (class "Default")
      (node (ref "D29") (pin "2") (pinfunction "A_2") (pintype "unspecified"))
      (node (ref "SW29") (pin "2") (pinfunction "2_2") (pintype "unspecified"))
    )
    (net (code "45") (name "Net-(D30-A)") (class "Default")
      (node (ref "D30") (pin "2") (pinfunction "A_2") (pintype "unspecified"))
      (node (ref "SW30") (pin "2") (pinfunction "2_2") (pintype "unspecified"))
    )
    (net (code "46") (name "Net-(D31-A)") (class "Default")
      (node (ref "D31") (pin "2") (pinfunction "A_2") (pintype "unspecified"))
      (node (ref "SW31") (pin "2") (pinfunction "2_2") (pintype "unspecified"))
    )
    (net (code "47") (name "Net-(D32-A)") (class "Default")
      (node (ref "D32") (pin "2") (pinfunction "A_2") (pintype "unspecified"))
      (node (ref "SW32") (pin "2") (pinfunction "2_2") (pintype "unspecified"))
    )
    (net (code "48") (name "Net-(D33-A)") (class "Default")
      (node (ref "D33") (pin "2") (pinfunction "A_2") (pintype "unspecified"))
      (node (ref "SW33") (pin "2") (pinfunction "2_2") (pintype "unspecified"))
    )
    (net (code "49") (name "Net-(D34-A)") (class "Default")
      (node (ref "D34") (pin "2") (pinfunction "A_2") (pintype "unspecified"))
      (node (ref "SW34") (pin "2") (pinfunction "2_2") (pintype "unspecified"))
    )
    (net (code "50") (name "Net-(D35-A)") (class "Default")
      (node (ref "D35") (pin "2") (pinfunction "A_2") (pintype "unspecified"))
      (node (ref "SW35") (pin "2") (pinfunction "2_2") (pintype "unspecified"))
    )
    (net (code "51") (name "Net-(D36-A)") (class "Default")
      (node (ref "D36") (pin "2") (pinfunction "A_2") (pintype "unspecified"))
      (node (ref "SW36") (pin "2") (pinfunction "2_2") (pintype "unspecified"))
    )
    (net (code "52") (name "Net-(D37-A)") (class "Default")
      (node (ref "D37") (pin "2") (pinfunction "A_2") (pintype "unspecified"))
      (node (ref "SW37") (pin "2") (pinfunction "2_2") (pintype "unspecified"))
    )
    (net (code "53") (name "Net-(D38-A)") (class "Default")
      (node (ref "D38") (pin "2") (pinfunction "A_2") (pintype "unspecified"))
      (node (ref "SW38") (pin "2") (pinfunction "2_2") (pintype "unspecified"))
    )
    (net (code "54") (name "Net-(D39-A)") (class "Default")
      (node (ref "D39") (pin "2") (pinfunction "A_2") (pintype "unspecified"))
      (node (ref "SW39") (pin "2") (pinfunction "2_2") (pintype "unspecified"))
    )
    (net (code "55") (name "Net-(D40-A)") (class "Default")
      (node (ref "D40") (pin "2") (pinfunction "A_2") (pintype "unspecified"))
      (node (ref "SW40") (pin "2") (pinfunction "2_2") (pintype "unspecified"))
    )
    (net (code "56") (name "Net-(D41-A)") (class "Default")
      (node (ref "D41") (pin "2") (pinfunction "A_2") (pintype "unspecified"))
      (node (ref "SW41") (pin "2") (pinfunction "2_2") (pintype "unspecified"))
    )
    (net (code "57") (name "Net-(D42-A)") (class "Default")
      (node (ref "D42") (pin "2") (pinfunction "A_2") (pintype "unspecified"))
      (node (ref "SW42") (pin "2") (pinfunction "2_2") (pintype "unspecified"))
    )
    (net (code "58") (name "Net-(D43-A)") (class "Default")
      (node (ref "D43") (pin "2") (pinfunction "A_2") (pintype "unspecified"))
      (node (ref "SW43") (pin "2") (pinfunction "2_2") (pintype "unspecified"))
    )
    (net (code "59") (name "Net-(D44-A)") (class "Default")
      (node (ref "D44") (pin "2") (pinfunction "A_2") (pintype "unspecified"))
      (node (ref "SW44") (pin "2") (pinfunction "2_2") (pintype "unspecified"))
    )
    (net (code "60") (name "Net-(D45-A)") (class "Default")
      (node (ref "D45") (pin "2") (pinfunction "A_2") (pintype "unspecified"))
      (node (ref "SW45") (pin "2") (pinfunction "2_2") (pintype "unspecified"))
    )
    (net (code "61") (name "Net-(D46-A)") (class "Default")
      (node (ref "D46") (pin "2") (pinfunction "A_2") (pintype "unspecified"))
      (node (ref "SW46") (pin "2") (pinfunction "2_2") (pintype "unspecified"))
    )
    (net (code "62") (name "Net-(D47-A)") (class "Default")
      (node (ref "D47") (pin "2") (pinfunction "A_2") (pintype "unspecified"))
      (node (ref "SW47") (pin "2") (pinfunction "2_2") (pintype "unspecified"))
    )
    (net (code "63") (name "Net-(D48-A)") (class "Default")
      (node (ref "D48") (pin "2") (pinfunction "A_2") (pintype "unspecified"))
      (node (ref "SW48") (pin "2") (pinfunction "2_2") (pintype "unspecified"))
    )
    (net (code "64") (name "Net-(D49-A)") (class "Default")
      (node (ref "D49") (pin "2") (pinfunction "A_2") (pintype "unspecified"))
      (node (ref "SW49") (pin "2") (pinfunction "2_2") (pintype "unspecified"))
    )
    (net (code "65") (name "Net-(D50-A)") (class "Default")
      (node (ref "D50") (pin "2") (pinfunction "A_2") (pintype "unspecified"))
      (node (ref "SW50") (pin "2") (pinfunction "2_2") (pintype "unspecified"))
    )
    (net (code "66") (name "Net-(D51-A)") (class "Default")
      (node (ref "D51") (pin "2") (pinfunction "A_2") (pintype "unspecified"))
      (node (ref "SW51") (pin "2") (pinfunction "2_2") (pintype "unspecified"))
    )
    (net (code "67") (name "Net-(D52-A)") (class "Default")
      (node (ref "D52") (pin "2") (pinfunction "A_2") (pintype "unspecified"))
      (node (ref "SW52") (pin "2") (pinfunction "2_2") (pintype "unspecified"))
    )
    (net (code "68") (name "Net-(D53-A)") (class "Default")
      (node (ref "D53") (pin "2") (pinfunction "A_2") (pintype "unspecified"))
      (node (ref "SW53") (pin "2") (pinfunction "2_2") (pintype "unspecified"))
    )
    (net (code "69") (name "Net-(D54-A)") (class "Default")
      (node (ref "D54") (pin "2") (pinfunction "A_2") (pintype "unspecified"))
      (node (ref "SW54") (pin "2") (pinfunction "2_2") (pintype "unspecified"))
    )
    (net (code "70") (name "Net-(D55-A)") (class "Default")
      (node (ref "D55") (pin "2") (pinfunction "A_2") (pintype "unspecified"))
      (node (ref "SW55") (pin "2") (pinfunction "2_2") (pintype "unspecified"))
    )
    (net (code "71") (name "Net-(D56-A)") (class "Default")
      (node (ref "D56") (pin "2") (pinfunction "A_2") (pintype "unspecified"))
      (node (ref "SW56") (pin "2") (pinfunction "2_2") (pintype "unspecified"))
    )
    (net (code "72") (name "Net-(D57-A)") (class "Default")
      (node (ref "D57") (pin "2") (pinfunction "A_2") (pintype "unspecified"))
      (node (ref "SW57") (pin "2") (pinfunction "2_2") (pintype "unspecified"))
    )
    (net (code "73") (name "Net-(D58-A)") (class "Default")
      (node (ref "D58") (pin "2") (pinfunction "A_2") (pintype "unspecified"))
      (node (ref "SW58") (pin "2") (pinfunction "2_2") (pintype "unspecified"))
    )
    (net (code "74") (name "Net-(D59-A)") (class "Default")
      (node (ref "D59") (pin "2") (pinfunction "A_2") (pintype "unspecified"))
      (node (ref "SW59") (pin "2") (pinfunction "2_2") (pintype "unspecified"))
    )
    (net (code "75") (name "Net-(D60-A)") (class "Default")
      (node (ref "D60") (pin "2") (pinfunction "A_2") (pintype "unspecified"))
      (node (ref "SW60") (pin "2") (pinfunction "2_2") (pintype "unspecified"))
    )
    (net (code "76") (name "Net-(D61-A)") (class "Default")
      (node (ref "D61") (pin "2") (pinfunction "A_2") (pintype "unspecified"))
      (node (ref "SW61") (pin "2") (pinfunction "2_2") (pintype "unspecified"))
    )
    (net (code "77") (name "Net-(D62-A)") (class "Default")
      (node (ref "D62") (pin "2") (pinfunction "A_2") (pintype "unspecified"))
      (node (ref "SW62") (pin "2") (pinfunction "2_2") (pintype "unspecified"))
    )
    (net (code "78") (name "R0") (class "Default")
      (node (ref "D1") (pin "1") (pinfunction "K_1") (pintype "unspecified"))
      (node (ref "D10") (pin "1") (pinfunction "K_1") (pintype "unspecified"))
      (node (ref "D11") (pin "1") (pinfunction "K_1") (pintype "unspecified"))
      (node (ref "D12") (pin "1") (pinfunction "K_1") (pintype "unspecified"))
      (node (ref "D13") (pin "1") (pinfunction "K_1") (pintype "unspecified"))
      (node (ref "D14") (pin "1") (pinfunction "K_1") (pintype "unspecified"))
      (node (ref "D2") (pin "1") (pinfunction "K_1") (pintype "unspecified"))
      (node (ref "D3") (pin "1") (pinfunction "K_1") (pintype "unspecified"))
      (node (ref "D4") (pin "1") (pinfunction "K_1") (pintype "unspecified"))
      (node (ref "D5") (pin "1") (pinfunction "K_1") (pintype "unspecified"))
      (node (ref "D6") (pin "1") (pinfunction "K_1") (pintype "unspecified"))
      (node (ref "D7") (pin "1") (pinfunction "K_1") (pintype "unspecified"))
      (node (ref "D8") (pin "1") (pinfunction "K_1") (pintype "unspecified"))
      (node (ref "D9") (pin "1") (pinfunction "K_1") (pintype "unspecified"))
      (node (ref "U1") (pin "21") (pinfunction "GPIO16_21") (pintype "bidirectional"))
    )
    (net (code "79") (name "R1") (class "Default")
      (node (ref "D15") (pin "1") (pinfunction "K_1") (pintype "unspecified"))
      (node (ref "D16") (pin "1") (pinfunction "K_1") (pintype "unspecified"))
      (node (ref "D17") (pin "1") (pinfunction "K_1") (pintype "unspecified"))
      (node (ref "D18") (pin "1") (pinfunction "K_1") (pintype "unspecified"))
      (node (ref "D19") (pin "1") (pinfunction "K_1") (pintype "unspecified"))
      (node (ref "D20") (pin "1") (pinfunction "K_1") (pintype "unspecified"))
      (node (ref "D21") (pin "1") (pinfunction "K_1") (pintype "unspecified"))
      (node (ref "D22") (pin "1") (pinfunction "K_1") (pintype "unspecified"))
      (node (ref "D23") (pin "1") (pinfunction "K_1") (pintype "unspecified"))
      (node (ref "D24") (pin "1") (pinfunction "K_1") (pintype "unspecified"))
      (node (ref "D25") (pin "1") (pinfunction "K_1") (pintype "unspecified"))
      (node (ref "D26") (pin "1") (pinfunction "K_1") (pintype "unspecified"))
      (node (ref "D27") (pin "1") (pinfunction "K_1") (pintype "unspecified"))
      (node (ref "D28") (pin "1") (pinfunction "K_1") (pintype "unspecified"))
      (node (ref "U1") (pin "22") (pinfunction "GPIO17_22") (pintype "bidirectional"))
    )
    (net (code "80") (name "R2") (class "Default")
      (node (ref "D29") (pin "1") (pinfunction "K_1") (pintype "unspecified"))
      (node (ref "D30") (pin "1") (pinfunction "K_1") (pintype "unspecified"))
      (node (ref "D31") (pin "1") (pinfunction "K_1") (pintype "unspecified"))
      (node (ref "D32") (pin "1") (pinfunction "K_1") (pintype "unspecified"))
      (node (ref "D33") (pin "1") (pinfunction "K_1") (pintype "unspecified"))
      (node (ref "D34") (pin "1") (pinfunction "K_1") (pintype "unspecified"))
      (node (ref "D35") (pin "1") (pinfunction "K_1") (pintype "unspecified"))
      (node (ref "D36") (pin "1") (pinfunction "K_1") (pintype "unspecified"))
      (node (ref "D37") (pin "1") (pinfunction "K_1") (pintype "unspecified"))
      (node (ref "D38") (pin "1") (pinfunction "K_1") (pintype "unspecified"))
      (node (ref "D39") (pin "1") (pinfunction "K_1") (pintype "unspecified"))
      (node (ref "D40") (pin "1") (pinfunction "K_1") (pintype "unspecified"))
      (node (ref "D41") (pin "1") (pinfunction "K_1") (pintype "unspecified"))
      (node (ref "U1") (pin "31") (pinfunction "GPIO26_ADC0_31") (pintype "bidirectional"))
    )
    (net (code "81") (name "R3") (class "Default")
      (node (ref "D42") (pin "1") (pinfunction "K_1") (pintype "unspecified"))
      (node (ref "D43") (pin "1") (pinfunction "K_1") (pintype "unspecified"))
      (node (ref "D44") (pin "1") (pinfunction "K_1") (pintype "unspecified"))
      (node (ref "D45") (pin "1") (pinfunction "K_1") (pintype "unspecified"))
      (node (ref "D46") (pin "1") (pinfunction "K_1") (pintype "unspecified"))
      (node (ref "D47") (pin "1") (pinfunction "K_1") (pintype "unspecified"))
      (node (ref "D48") (pin "1") (pinfunction "K_1") (pintype "unspecified"))
      (node (ref "D49") (pin "1") (pinfunction "K_1") (pintype "unspecified"))
      (node (ref "D50") (pin "1") (pinfunction "K_1") (pintype "unspecified"))
      (node (ref "D51") (pin "1") (pinfunction "K_1") (pintype "unspecified"))
      (node (ref "D52") (pin "1") (pinfunction "K_1") (pintype "unspecified"))
      (node (ref "D53") (pin "1") (pinfunction "K_1") (pintype "unspecified"))
      (node (ref "D54") (pin "1") (pinfunction "K_1") (pintype "unspecified"))
      (node (ref "U1") (pin "29") (pinfunction "GPIO22_29") (pintype "bidirectional"))
    )
    (net (code "82") (name "R4") (class "Default")
      (node (ref "D55") (pin "1") (pinfunction "K_1") (pintype "unspecified"))
      (node (ref "D56") (pin "1") (pinfunction "K_1") (pintype "unspecified"))
      (node (ref "D57") (pin "1") (pinfunction "K_1") (pintype "unspecified"))
      (node (ref "D58") (pin "1") (pinfunction "K_1") (pintype "unspecified"))
      (node (ref "D59") (pin "1") (pinfunction "K_1") (pintype "unspecified"))
      (node (ref "D60") (pin "1") (pinfunction "K_1") (pintype "unspecified"))
      (node (ref "D61") (pin "1") (pinfunction "K_1") (pintype "unspecified"))
      (node (ref "D62") (pin "1") (pinfunction "K_1") (pintype "unspecified"))
      (node (ref "U1") (pin "32") (pinfunction "GPIO27_ADC1_32") (pintype "bidirectional"))
    )
    (net (code "83") (name "unconnected-(U1-3V3-Pad36)") (class "Default")
      (node (ref "U1") (pin "36") (pinfunction "3V3_36") (pintype "unspecified"))
    )
    (net (code "84") (name "unconnected-(U1-3V3_EN-Pad37)") (class "Default")
      (node (ref "U1") (pin "37") (pinfunction "3V3_EN_37") (pintype "input"))
    )
    (net (code "85") (name "unconnected-(U1-ADC_VREF-Pad35)") (class "Default")
      (node (ref "U1") (pin "35") (pinfunction "ADC_VREF_35") (pintype "unspecified"))
    )
    (net (code "86") (name "unconnected-(U1-GND-Pad42)") (class "Default")
      (node (ref "U1") (pin "42") (pinfunction "GND_42") (pintype "unspecified"))
    )
    (net (code "87") (name "unconnected-(U1-GPIO2-Pad4)") (class "Default")
      (node (ref "U1") (pin "4") (pinfunction "GPIO2_4") (pintype "bidirectional"))
    )
    (net (code "88") (name "unconnected-(U1-GPIO3-Pad5)") (class "Default")
      (node (ref "U1") (pin "5") (pinfunction "GPIO3_5") (pintype "bidirectional"))
    )
    (net (code "89") (name "unconnected-(U1-GPIO18-Pad24)") (class "Default")
      (node (ref "U1") (pin "24") (pinfunction "GPIO18_24") (pintype "bidirectional"))
    )
    (net (code "90") (name "unconnected-(U1-GPIO19-Pad25)") (class "Default")
      (node (ref "U1") (pin "25") (pinfunction "GPIO19_25") (pintype "bidirectional"))
    )
    (net (code "91") (name "unconnected-(U1-GPIO20-Pad26)") (class "Default")
      (node (ref "U1") (pin "26") (pinfunction "GPIO20_26") (pintype "bidirectional"))
    )
    (net (code "92") (name "unconnected-(U1-GPIO21-Pad27)") (class "Default")
      (node (ref "U1") (pin "27") (pinfunction "GPIO21_27") (pintype "bidirectional"))
    )
    (net (code "93") (name "unconnected-(U1-GPIO28_ADC2-Pad34)") (class "Default")
      (node (ref "U1") (pin "34") (pinfunction "GPIO28_ADC2_34") (pintype "bidirectional"))
    )
    (net (code "94") (name "unconnected-(U1-RUN-Pad30)") (class "Default")
      (node (ref "U1") (pin "30") (pinfunction "RUN_30") (pintype "input"))
    )
    (net (code "95") (name "unconnected-(U1-SWCLK-Pad41)") (class "Default")
      (node (ref "U1") (pin "41") (pinfunction "SWCLK_41") (pintype "input"))
    )
    (net (code "96") (name "unconnected-(U1-SWDIO-Pad43)") (class "Default")
      (node (ref "U1") (pin "43") (pinfunction "SWDIO_43") (pintype "bidirectional"))
    )
    (net (code "97") (name "unconnected-(U1-VBUS-Pad40)") (class "Default")
      (node (ref "U1") (pin "40") (pinfunction "VBUS_40") (pintype "unspecified"))
    )
    (net (code "98") (name "unconnected-(U1-VSYS-Pad39)") (class "Default")
      (node (ref "U1") (pin "39") (pinfunction "VSYS_39") (pintype "unspecified"))
    )
  )
)
